# PRUC-Voltmeter_FPGA-Power.net
KiCad netlist of a schematic drawn in Altium Designer
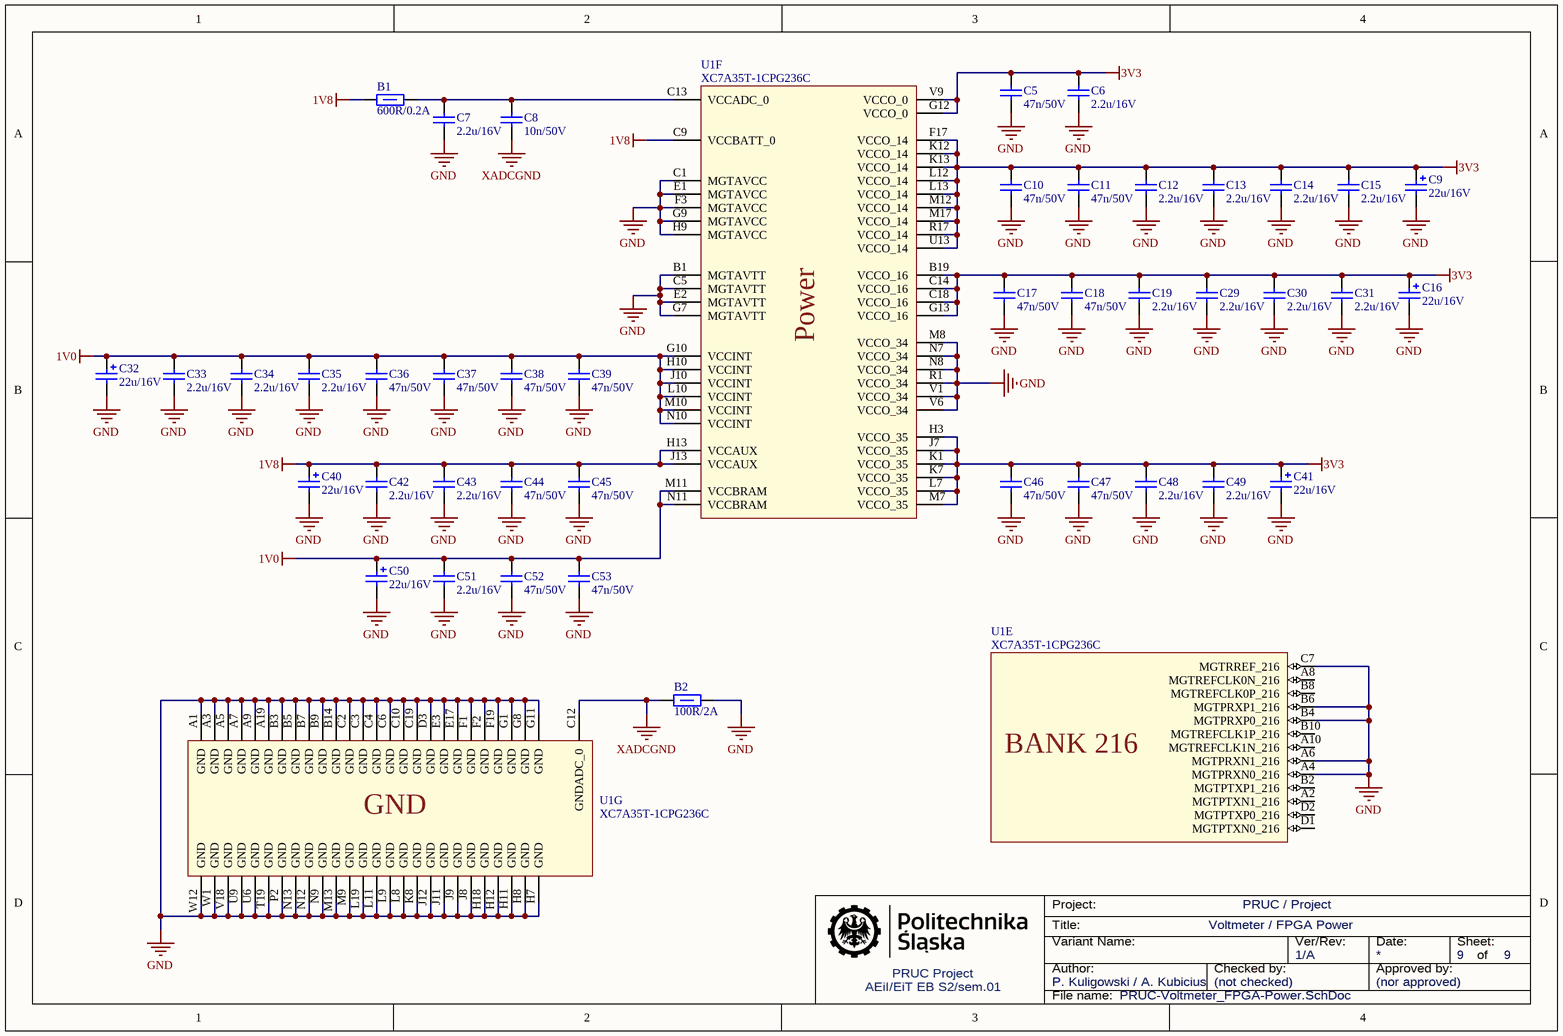
[diagram p0: PRUC-Voltmeter_FPGA-Power.SchDoc]

(export (version "E")
  (design (tool "Eeschema 10.0.6"))
  (components
    (comp (ref "B1")
      (value "600R/0.2A")
      (footprint "FerriteBead_1206")
      (fields
        (field (name "PART NUMBER") "BLM31A601SPT")
        (field (name "MANUFACTURER") "Murata")
        (field (name "MANUFACTURER PART NUMBER") "BLM31AJ601SN1L")
      )
      (libsource (lib "kplabs") (part "FerriteBead"))
    )
    (comp (ref "B2")
      (value "100R/2A")
      (footprint "FerriteBead_0603")
      (fields (field (name "PART NUMBER") "BLM18EG101TN1D") (field (name "MANUFACTURER") "Murata"))
      (libsource (lib "") (part "FerriteBead_1"))
    )
    (comp (ref "C5")
      (value "47n/50V")
      (footprint "MLCC_0603")
      (fields (field (name "PART NUMBER") "CL10B473KB8NNNC") (field (name "MANUFACTURER") "Samsung"))
      (libsource (lib "kplabs") (part "Cap"))
    )
    (comp (ref "C6")
      (value "2.2u/16V")
      (footprint "MLCC_0603")
      (fields (field (name "PART NUMBER") "CL10A225KO8NNNC") (field (name "MANUFACTURER") "Samsung"))
      (libsource (lib "kplabs") (part "Cap"))
    )
    (comp (ref "C7")
      (value "2.2u/16V")
      (footprint "MLCC_0603")
      (fields (field (name "PART NUMBER") "CL10A225KO8NNNC") (field (name "MANUFACTURER") "Samsung"))
      (libsource (lib "kplabs") (part "Cap"))
    )
    (comp (ref "C8")
      (value "10n/50V")
      (footprint "MLCC_0603")
      (fields (field (name "PART NUMBER") "CL10B103KB8NNNC") (field (name "MANUFACTURER") "Samsung"))
      (libsource (lib "kplabs") (part "Cap"))
    )
    (comp (ref "C9")
      (value "22u/16V")
      (footprint "Tantalum_B")
      (fields
        (field (name "PART NUMBER") "TAJB226K016R")
        (field (name "MANUFACTURER") "AVX")
        (field (name "MANUFACTURER PART NUMBER") "TAJB226K016RNJ")
      )
      (libsource (lib "kplabs") (part "Cap_Pol"))
    )
    (comp (ref "C10")
      (value "47n/50V")
      (footprint "MLCC_0603")
      (fields (field (name "PART NUMBER") "CL10B473KB8NNNC") (field (name "MANUFACTURER") "Samsung"))
      (libsource (lib "kplabs") (part "Cap"))
    )
    (comp (ref "C11")
      (value "47n/50V")
      (footprint "MLCC_0603")
      (fields (field (name "PART NUMBER") "CL10B473KB8NNNC") (field (name "MANUFACTURER") "Samsung"))
      (libsource (lib "kplabs") (part "Cap"))
    )
    (comp (ref "C12")
      (value "2.2u/16V")
      (footprint "MLCC_0603")
      (fields (field (name "PART NUMBER") "CL10A225KO8NNNC") (field (name "MANUFACTURER") "Samsung"))
      (libsource (lib "kplabs") (part "Cap"))
    )
    (comp (ref "C13")
      (value "2.2u/16V")
      (footprint "MLCC_0603")
      (fields (field (name "PART NUMBER") "CL10A225KO8NNNC") (field (name "MANUFACTURER") "Samsung"))
      (libsource (lib "kplabs") (part "Cap"))
    )
    (comp (ref "C14")
      (value "2.2u/16V")
      (footprint "MLCC_0603")
      (fields (field (name "PART NUMBER") "CL10A225KO8NNNC") (field (name "MANUFACTURER") "Samsung"))
      (libsource (lib "kplabs") (part "Cap"))
    )
    (comp (ref "C15")
      (value "2.2u/16V")
      (footprint "MLCC_0603")
      (fields (field (name "PART NUMBER") "CL10A225KO8NNNC") (field (name "MANUFACTURER") "Samsung"))
      (libsource (lib "kplabs") (part "Cap"))
    )
    (comp (ref "C16")
      (value "22u/16V")
      (footprint "Tantalum_B")
      (fields
        (field (name "PART NUMBER") "TAJB226K016R")
        (field (name "MANUFACTURER") "AVX")
        (field (name "MANUFACTURER PART NUMBER") "TAJB226K016RNJ")
      )
      (libsource (lib "kplabs") (part "Cap_Pol"))
    )
    (comp (ref "C17")
      (value "47n/50V")
      (footprint "MLCC_0603")
      (fields (field (name "PART NUMBER") "CL10B473KB8NNNC") (field (name "MANUFACTURER") "Samsung"))
      (libsource (lib "kplabs") (part "Cap"))
    )
    (comp (ref "C18")
      (value "47n/50V")
      (footprint "MLCC_0603")
      (fields (field (name "PART NUMBER") "CL10B473KB8NNNC") (field (name "MANUFACTURER") "Samsung"))
      (libsource (lib "kplabs") (part "Cap"))
    )
    (comp (ref "C19")
      (value "2.2u/16V")
      (footprint "MLCC_0603")
      (fields (field (name "PART NUMBER") "CL10A225KO8NNNC") (field (name "MANUFACTURER") "Samsung"))
      (libsource (lib "kplabs") (part "Cap"))
    )
    (comp (ref "C29")
      (value "2.2u/16V")
      (footprint "MLCC_0603")
      (fields (field (name "PART NUMBER") "CL10A225KO8NNNC") (field (name "MANUFACTURER") "Samsung"))
      (libsource (lib "kplabs") (part "Cap"))
    )
    (comp (ref "C30")
      (value "2.2u/16V")
      (footprint "MLCC_0603")
      (fields (field (name "PART NUMBER") "CL10A225KO8NNNC") (field (name "MANUFACTURER") "Samsung"))
      (libsource (lib "kplabs") (part "Cap"))
    )
    (comp (ref "C31")
      (value "2.2u/16V")
      (footprint "MLCC_0603")
      (fields (field (name "PART NUMBER") "CL10A225KO8NNNC") (field (name "MANUFACTURER") "Samsung"))
      (libsource (lib "kplabs") (part "Cap"))
    )
    (comp (ref "C32")
      (value "22u/16V")
      (footprint "Tantalum_B")
      (fields
        (field (name "PART NUMBER") "TAJB226K016R")
        (field (name "MANUFACTURER") "AVX")
        (field (name "MANUFACTURER PART NUMBER") "TAJB226K016RNJ")
      )
      (libsource (lib "kplabs") (part "Cap_Pol"))
    )
    (comp (ref "C33")
      (value "2.2u/16V")
      (footprint "MLCC_0603")
      (fields (field (name "PART NUMBER") "CL10A225KO8NNNC") (field (name "MANUFACTURER") "Samsung"))
      (libsource (lib "kplabs") (part "Cap"))
    )
    (comp (ref "C34")
      (value "2.2u/16V")
      (footprint "MLCC_0603")
      (fields (field (name "PART NUMBER") "CL10A225KO8NNNC") (field (name "MANUFACTURER") "Samsung"))
      (libsource (lib "kplabs") (part "Cap"))
    )
    (comp (ref "C35")
      (value "2.2u/16V")
      (footprint "MLCC_0603")
      (fields (field (name "PART NUMBER") "CL10A225KO8NNNC") (field (name "MANUFACTURER") "Samsung"))
      (libsource (lib "kplabs") (part "Cap"))
    )
    (comp (ref "C36")
      (value "47n/50V")
      (footprint "MLCC_0603")
      (fields (field (name "PART NUMBER") "CL10B473KB8NNNC") (field (name "MANUFACTURER") "Samsung"))
      (libsource (lib "kplabs") (part "Cap"))
    )
    (comp (ref "C37")
      (value "47n/50V")
      (footprint "MLCC_0603")
      (fields (field (name "PART NUMBER") "CL10B473KB8NNNC") (field (name "MANUFACTURER") "Samsung"))
      (libsource (lib "kplabs") (part "Cap"))
    )
    (comp (ref "C38")
      (value "47n/50V")
      (footprint "MLCC_0603")
      (fields (field (name "PART NUMBER") "CL10B473KB8NNNC") (field (name "MANUFACTURER") "Samsung"))
      (libsource (lib "kplabs") (part "Cap"))
    )
    (comp (ref "C39")
      (value "47n/50V")
      (footprint "MLCC_0603")
      (fields (field (name "PART NUMBER") "CL10B473KB8NNNC") (field (name "MANUFACTURER") "Samsung"))
      (libsource (lib "kplabs") (part "Cap"))
    )
    (comp (ref "C40")
      (value "22u/16V")
      (footprint "Tantalum_B")
      (fields
        (field (name "PART NUMBER") "TAJB226K016R")
        (field (name "MANUFACTURER") "AVX")
        (field (name "MANUFACTURER PART NUMBER") "TAJB226K016RNJ")
      )
      (libsource (lib "kplabs") (part "Cap_Pol"))
    )
    (comp (ref "C41")
      (value "22u/16V")
      (footprint "Tantalum_B")
      (fields
        (field (name "PART NUMBER") "TAJB226K016R")
        (field (name "MANUFACTURER") "AVX")
        (field (name "MANUFACTURER PART NUMBER") "TAJB226K016RNJ")
      )
      (libsource (lib "kplabs") (part "Cap_Pol"))
    )
    (comp (ref "C42")
      (value "2.2u/16V")
      (footprint "MLCC_0603")
      (fields (field (name "PART NUMBER") "CL10A225KO8NNNC") (field (name "MANUFACTURER") "Samsung"))
      (libsource (lib "kplabs") (part "Cap"))
    )
    (comp (ref "C43")
      (value "2.2u/16V")
      (footprint "MLCC_0603")
      (fields (field (name "PART NUMBER") "CL10A225KO8NNNC") (field (name "MANUFACTURER") "Samsung"))
      (libsource (lib "kplabs") (part "Cap"))
    )
    (comp (ref "C44")
      (value "47n/50V")
      (footprint "MLCC_0603")
      (fields (field (name "PART NUMBER") "CL10B473KB8NNNC") (field (name "MANUFACTURER") "Samsung"))
      (libsource (lib "kplabs") (part "Cap"))
    )
    (comp (ref "C45")
      (value "47n/50V")
      (footprint "MLCC_0603")
      (fields (field (name "PART NUMBER") "CL10B473KB8NNNC") (field (name "MANUFACTURER") "Samsung"))
      (libsource (lib "kplabs") (part "Cap"))
    )
    (comp (ref "C46")
      (value "47n/50V")
      (footprint "MLCC_0603")
      (fields (field (name "PART NUMBER") "CL10B473KB8NNNC") (field (name "MANUFACTURER") "Samsung"))
      (libsource (lib "kplabs") (part "Cap"))
    )
    (comp (ref "C47")
      (value "47n/50V")
      (footprint "MLCC_0603")
      (fields (field (name "PART NUMBER") "CL10B473KB8NNNC") (field (name "MANUFACTURER") "Samsung"))
      (libsource (lib "kplabs") (part "Cap"))
    )
    (comp (ref "C48")
      (value "2.2u/16V")
      (footprint "MLCC_0603")
      (fields (field (name "PART NUMBER") "CL10A225KO8NNNC") (field (name "MANUFACTURER") "Samsung"))
      (libsource (lib "kplabs") (part "Cap"))
    )
    (comp (ref "C49")
      (value "2.2u/16V")
      (footprint "MLCC_0603")
      (fields (field (name "PART NUMBER") "CL10A225KO8NNNC") (field (name "MANUFACTURER") "Samsung"))
      (libsource (lib "kplabs") (part "Cap"))
    )
    (comp (ref "C50")
      (value "22u/16V")
      (footprint "Tantalum_B")
      (fields
        (field (name "PART NUMBER") "TAJB226K016R")
        (field (name "MANUFACTURER") "AVX")
        (field (name "MANUFACTURER PART NUMBER") "TAJB226K016RNJ")
      )
      (libsource (lib "kplabs") (part "Cap_Pol"))
    )
    (comp (ref "C51")
      (value "2.2u/16V")
      (footprint "MLCC_0603")
      (fields (field (name "PART NUMBER") "CL10A225KO8NNNC") (field (name "MANUFACTURER") "Samsung"))
      (libsource (lib "kplabs") (part "Cap"))
    )
    (comp (ref "C52")
      (value "47n/50V")
      (footprint "MLCC_0603")
      (fields (field (name "PART NUMBER") "CL10B473KB8NNNC") (field (name "MANUFACTURER") "Samsung"))
      (libsource (lib "kplabs") (part "Cap"))
    )
    (comp (ref "C53")
      (value "47n/50V")
      (footprint "MLCC_0603")
      (fields (field (name "PART NUMBER") "CL10B473KB8NNNC") (field (name "MANUFACTURER") "Samsung"))
      (libsource (lib "kplabs") (part "Cap"))
    )
    (comp (ref "U1")
      (value "XC7A35T-1CPG236C")
      (footprint "CPG236-0.5mm")
      (fields (field (name "MANUFACTURER") "Xilinx"))
      (libsource (lib "kplabs") (part "XC7A35T-1CPG236C"))
    )
  )
  (nets
    (net (code "1") (name "1V0") (class "Default")
      (node (ref "C32") (pin "1") (pinfunction "1_1") (pintype "passive"))
      (node (ref "C33") (pin "1") (pinfunction "1_1") (pintype "passive"))
      (node (ref "C34") (pin "1") (pinfunction "1_1") (pintype "passive"))
      (node (ref "C35") (pin "1") (pinfunction "1_1") (pintype "passive"))
      (node (ref "C36") (pin "1") (pinfunction "1_1") (pintype "passive"))
      (node (ref "C37") (pin "1") (pinfunction "1_1") (pintype "passive"))
      (node (ref "C38") (pin "1") (pinfunction "1_1") (pintype "passive"))
      (node (ref "C39") (pin "1") (pinfunction "1_1") (pintype "passive"))
      (node (ref "C50") (pin "1") (pinfunction "1_1") (pintype "passive"))
      (node (ref "C51") (pin "1") (pinfunction "1_1") (pintype "passive"))
      (node (ref "C52") (pin "1") (pinfunction "1_1") (pintype "passive"))
      (node (ref "C53") (pin "1") (pinfunction "1_1") (pintype "passive"))
      (node (ref "U1") (pin "G10") (pinfunction "VCCINT_G10") (pintype "power_in"))
      (node (ref "U1") (pin "H10") (pinfunction "VCCINT_H10") (pintype "power_in"))
      (node (ref "U1") (pin "J10") (pinfunction "VCCINT_J10") (pintype "power_in"))
      (node (ref "U1") (pin "L10") (pinfunction "VCCINT_L10") (pintype "power_in"))
      (node (ref "U1") (pin "M10") (pinfunction "VCCINT_M10") (pintype "power_in"))
      (node (ref "U1") (pin "M11") (pinfunction "VCCBRAM_M11") (pintype "power_in"))
      (node (ref "U1") (pin "N10") (pinfunction "VCCINT_N10") (pintype "power_in"))
      (node (ref "U1") (pin "N11") (pinfunction "VCCBRAM_N11") (pintype "power_in"))
    )
    (net (code "2") (name "1V8") (class "Default")
      (node (ref "B1") (pin "2") (pinfunction "2_2") (pintype "passive"))
      (node (ref "C40") (pin "1") (pinfunction "1_1") (pintype "passive"))
      (node (ref "C42") (pin "1") (pinfunction "1_1") (pintype "passive"))
      (node (ref "C43") (pin "1") (pinfunction "1_1") (pintype "passive"))
      (node (ref "C44") (pin "1") (pinfunction "1_1") (pintype "passive"))
      (node (ref "C45") (pin "1") (pinfunction "1_1") (pintype "passive"))
      (node (ref "U1") (pin "C9") (pinfunction "VCCBATT_0_C9") (pintype "power_in"))
      (node (ref "U1") (pin "H13") (pinfunction "VCCAUX_H13") (pintype "power_in"))
      (node (ref "U1") (pin "J13") (pinfunction "VCCAUX_J13") (pintype "power_in"))
    )
    (net (code "3") (name "3V3") (class "Default")
      (node (ref "C10") (pin "1") (pinfunction "1_1") (pintype "passive"))
      (node (ref "C11") (pin "1") (pinfunction "1_1") (pintype "passive"))
      (node (ref "C12") (pin "1") (pinfunction "1_1") (pintype "passive"))
      (node (ref "C13") (pin "1") (pinfunction "1_1") (pintype "passive"))
      (node (ref "C14") (pin "1") (pinfunction "1_1") (pintype "passive"))
      (node (ref "C15") (pin "1") (pinfunction "1_1") (pintype "passive"))
      (node (ref "C16") (pin "1") (pinfunction "1_1") (pintype "passive"))
      (node (ref "C17") (pin "1") (pinfunction "1_1") (pintype "passive"))
      (node (ref "C18") (pin "1") (pinfunction "1_1") (pintype "passive"))
      (node (ref "C19") (pin "1") (pinfunction "1_1") (pintype "passive"))
      (node (ref "C29") (pin "1") (pinfunction "1_1") (pintype "passive"))
      (node (ref "C30") (pin "1") (pinfunction "1_1") (pintype "passive"))
      (node (ref "C31") (pin "1") (pinfunction "1_1") (pintype "passive"))
      (node (ref "C41") (pin "1") (pinfunction "1_1") (pintype "passive"))
      (node (ref "C46") (pin "1") (pinfunction "1_1") (pintype "passive"))
      (node (ref "C47") (pin "1") (pinfunction "1_1") (pintype "passive"))
      (node (ref "C48") (pin "1") (pinfunction "1_1") (pintype "passive"))
      (node (ref "C49") (pin "1") (pinfunction "1_1") (pintype "passive"))
      (node (ref "C5") (pin "1") (pinfunction "1_1") (pintype "passive"))
      (node (ref "C6") (pin "1") (pinfunction "1_1") (pintype "passive"))
      (node (ref "C9") (pin "1") (pinfunction "1_1") (pintype "passive"))
      (node (ref "U1") (pin "B19") (pinfunction "VCCO_16_B19") (pintype "power_in"))
      (node (ref "U1") (pin "C14") (pinfunction "VCCO_16_C14") (pintype "power_in"))
      (node (ref "U1") (pin "C18") (pinfunction "VCCO_16_C18") (pintype "power_in"))
      (node (ref "U1") (pin "F17") (pinfunction "VCCO_14_F17") (pintype "power_in"))
      (node (ref "U1") (pin "G12") (pinfunction "VCCO_0_G12") (pintype "power_in"))
      (node (ref "U1") (pin "G13") (pinfunction "VCCO_16_G13") (pintype "power_in"))
      (node (ref "U1") (pin "H3") (pinfunction "VCCO_35_H3") (pintype "power_in"))
      (node (ref "U1") (pin "J7") (pinfunction "VCCO_35_J7") (pintype "power_in"))
      (node (ref "U1") (pin "K1") (pinfunction "VCCO_35_K1") (pintype "power_in"))
      (node (ref "U1") (pin "K12") (pinfunction "VCCO_14_K12") (pintype "power_in"))
      (node (ref "U1") (pin "K13") (pinfunction "VCCO_14_K13") (pintype "power_in"))
      (node (ref "U1") (pin "K7") (pinfunction "VCCO_35_K7") (pintype "power_in"))
      (node (ref "U1") (pin "L12") (pinfunction "VCCO_14_L12") (pintype "power_in"))
      (node (ref "U1") (pin "L13") (pinfunction "VCCO_14_L13") (pintype "power_in"))
      (node (ref "U1") (pin "L7") (pinfunction "VCCO_35_L7") (pintype "power_in"))
      (node (ref "U1") (pin "M12") (pinfunction "VCCO_14_M12") (pintype "power_in"))
      (node (ref "U1") (pin "M17") (pinfunction "VCCO_14_M17") (pintype "power_in"))
      (node (ref "U1") (pin "M7") (pinfunction "VCCO_35_M7") (pintype "power_in"))
      (node (ref "U1") (pin "R17") (pinfunction "VCCO_14_R17") (pintype "power_in"))
      (node (ref "U1") (pin "U13") (pinfunction "VCCO_14_U13") (pintype "power_in"))
      (node (ref "U1") (pin "V9") (pinfunction "VCCO_0_V9") (pintype "power_in"))
    )
    (net (code "4") (name "GND") (class "Default")
      (node (ref "B2") (pin "2") (pinfunction "2_2") (pintype "passive"))
      (node (ref "C10") (pin "2") (pinfunction "2_2") (pintype "passive"))
      (node (ref "C11") (pin "2") (pinfunction "2_2") (pintype "passive"))
      (node (ref "C12") (pin "2") (pinfunction "2_2") (pintype "passive"))
      (node (ref "C13") (pin "2") (pinfunction "2_2") (pintype "passive"))
      (node (ref "C14") (pin "2") (pinfunction "2_2") (pintype "passive"))
      (node (ref "C15") (pin "2") (pinfunction "2_2") (pintype "passive"))
      (node (ref "C16") (pin "2") (pinfunction "2_2") (pintype "passive"))
      (node (ref "C17") (pin "2") (pinfunction "2_2") (pintype "passive"))
      (node (ref "C18") (pin "2") (pinfunction "2_2") (pintype "passive"))
      (node (ref "C19") (pin "2") (pinfunction "2_2") (pintype "passive"))
      (node (ref "C29") (pin "2") (pinfunction "2_2") (pintype "passive"))
      (node (ref "C30") (pin "2") (pinfunction "2_2") (pintype "passive"))
      (node (ref "C31") (pin "2") (pinfunction "2_2") (pintype "passive"))
      (node (ref "C32") (pin "2") (pinfunction "2_2") (pintype "passive"))
      (node (ref "C33") (pin "2") (pinfunction "2_2") (pintype "passive"))
      (node (ref "C34") (pin "2") (pinfunction "2_2") (pintype "passive"))
      (node (ref "C35") (pin "2") (pinfunction "2_2") (pintype "passive"))
      (node (ref "C36") (pin "2") (pinfunction "2_2") (pintype "passive"))
      (node (ref "C37") (pin "2") (pinfunction "2_2") (pintype "passive"))
      (node (ref "C38") (pin "2") (pinfunction "2_2") (pintype "passive"))
      (node (ref "C39") (pin "2") (pinfunction "2_2") (pintype "passive"))
      (node (ref "C40") (pin "2") (pinfunction "2_2") (pintype "passive"))
      (node (ref "C41") (pin "2") (pinfunction "2_2") (pintype "passive"))
      (node (ref "C42") (pin "2") (pinfunction "2_2") (pintype "passive"))
      (node (ref "C43") (pin "2") (pinfunction "2_2") (pintype "passive"))
      (node (ref "C44") (pin "2") (pinfunction "2_2") (pintype "passive"))
      (node (ref "C45") (pin "2") (pinfunction "2_2") (pintype "passive"))
      (node (ref "C46") (pin "2") (pinfunction "2_2") (pintype "passive"))
      (node (ref "C47") (pin "2") (pinfunction "2_2") (pintype "passive"))
      (node (ref "C48") (pin "2") (pinfunction "2_2") (pintype "passive"))
      (node (ref "C49") (pin "2") (pinfunction "2_2") (pintype "passive"))
      (node (ref "C5") (pin "2") (pinfunction "2_2") (pintype "passive"))
      (node (ref "C50") (pin "2") (pinfunction "2_2") (pintype "passive"))
      (node (ref "C51") (pin "2") (pinfunction "2_2") (pintype "passive"))
      (node (ref "C52") (pin "2") (pinfunction "2_2") (pintype "passive"))
      (node (ref "C53") (pin "2") (pinfunction "2_2") (pintype "passive"))
      (node (ref "C6") (pin "2") (pinfunction "2_2") (pintype "passive"))
      (node (ref "C7") (pin "2") (pinfunction "2_2") (pintype "passive"))
      (node (ref "C9") (pin "2") (pinfunction "2_2") (pintype "passive"))
      (node (ref "U1") (pin "A1") (pinfunction "GND_A1") (pintype "power_in"))
      (node (ref "U1") (pin "A19") (pinfunction "GND_A19") (pintype "power_in"))
      (node (ref "U1") (pin "A3") (pinfunction "GND_A3") (pintype "power_in"))
      (node (ref "U1") (pin "A4") (pinfunction "MGTPRXN0_216_A4") (pintype "bidirectional"))
      (node (ref "U1") (pin "A5") (pinfunction "GND_A5") (pintype "power_in"))
      (node (ref "U1") (pin "A6") (pinfunction "MGTPRXN1_216_A6") (pintype "bidirectional"))
      (node (ref "U1") (pin "A7") (pinfunction "GND_A7") (pintype "power_in"))
      (node (ref "U1") (pin "A9") (pinfunction "GND_A9") (pintype "power_in"))
      (node (ref "U1") (pin "B1") (pinfunction "MGTAVTT_B1") (pintype "power_in"))
      (node (ref "U1") (pin "B14") (pinfunction "GND_B14") (pintype "power_in"))
      (node (ref "U1") (pin "B3") (pinfunction "GND_B3") (pintype "power_in"))
      (node (ref "U1") (pin "B4") (pinfunction "MGTPRXP0_216_B4") (pintype "bidirectional"))
      (node (ref "U1") (pin "B5") (pinfunction "GND_B5") (pintype "power_in"))
      (node (ref "U1") (pin "B6") (pinfunction "MGTPRXP1_216_B6") (pintype "bidirectional"))
      (node (ref "U1") (pin "B7") (pinfunction "GND_B7") (pintype "power_in"))
      (node (ref "U1") (pin "B9") (pinfunction "GND_B9") (pintype "power_in"))
      (node (ref "U1") (pin "C1") (pinfunction "MGTAVCC_C1") (pintype "power_in"))
      (node (ref "U1") (pin "C10") (pinfunction "GND_C10") (pintype "power_in"))
      (node (ref "U1") (pin "C19") (pinfunction "GND_C19") (pintype "power_in"))
      (node (ref "U1") (pin "C2") (pinfunction "GND_C2") (pintype "power_in"))
      (node (ref "U1") (pin "C3") (pinfunction "GND_C3") (pintype "power_in"))
      (node (ref "U1") (pin "C4") (pinfunction "GND_C4") (pintype "power_in"))
      (node (ref "U1") (pin "C5") (pinfunction "MGTAVTT_C5") (pintype "power_in"))
      (node (ref "U1") (pin "C6") (pinfunction "GND_C6") (pintype "power_in"))
      (node (ref "U1") (pin "C7") (pinfunction "MGTRREF_216_C7") (pintype "bidirectional"))
      (node (ref "U1") (pin "D3") (pinfunction "GND_D3") (pintype "power_in"))
      (node (ref "U1") (pin "E1") (pinfunction "MGTAVCC_E1") (pintype "power_in"))
      (node (ref "U1") (pin "E17") (pinfunction "GND_E17") (pintype "power_in"))
      (node (ref "U1") (pin "E2") (pinfunction "MGTAVTT_E2") (pintype "power_in"))
      (node (ref "U1") (pin "E3") (pinfunction "GND_E3") (pintype "power_in"))
      (node (ref "U1") (pin "F1") (pinfunction "GND_F1") (pintype "power_in"))
      (node (ref "U1") (pin "F19") (pinfunction "GND_F19") (pintype "power_in"))
      (node (ref "U1") (pin "F2") (pinfunction "GND_F2") (pintype "power_in"))
      (node (ref "U1") (pin "F3") (pinfunction "MGTAVCC_F3") (pintype "power_in"))
      (node (ref "U1") (pin "G1") (pinfunction "GND_G1") (pintype "power_in"))
      (node (ref "U1") (pin "G11") (pinfunction "GND_G11") (pintype "power_in"))
      (node (ref "U1") (pin "G7") (pinfunction "MGTAVTT_G7") (pintype "power_in"))
      (node (ref "U1") (pin "G8") (pinfunction "GND_G8") (pintype "power_in"))
      (node (ref "U1") (pin "G9") (pinfunction "MGTAVCC_G9") (pintype "power_in"))
      (node (ref "U1") (pin "H11") (pinfunction "GND_H11") (pintype "power_in"))
      (node (ref "U1") (pin "H12") (pinfunction "GND_H12") (pintype "power_in"))
      (node (ref "U1") (pin "H18") (pinfunction "GND_H18") (pintype "power_in"))
      (node (ref "U1") (pin "H7") (pinfunction "GND_H7") (pintype "power_in"))
      (node (ref "U1") (pin "H8") (pinfunction "GND_H8") (pintype "power_in"))
      (node (ref "U1") (pin "H9") (pinfunction "MGTAVCC_H9") (pintype "power_in"))
      (node (ref "U1") (pin "J11") (pinfunction "GND_J11") (pintype "power_in"))
      (node (ref "U1") (pin "J12") (pinfunction "GND_J12") (pintype "power_in"))
      (node (ref "U1") (pin "J8") (pinfunction "GND_J8") (pintype "power_in"))
      (node (ref "U1") (pin "J9") (pinfunction "GND_J9") (pintype "power_in"))
      (node (ref "U1") (pin "K8") (pinfunction "GND_K8") (pintype "power_in"))
      (node (ref "U1") (pin "L11") (pinfunction "GND_L11") (pintype "power_in"))
      (node (ref "U1") (pin "L19") (pinfunction "GND_L19") (pintype "power_in"))
      (node (ref "U1") (pin "L8") (pinfunction "GND_L8") (pintype "power_in"))
      (node (ref "U1") (pin "L9") (pinfunction "GND_L9") (pintype "power_in"))
      (node (ref "U1") (pin "M13") (pinfunction "GND_M13") (pintype "power_in"))
      (node (ref "U1") (pin "M8") (pinfunction "VCCO_34_M8") (pintype "power_in"))
      (node (ref "U1") (pin "M9") (pinfunction "GND_M9") (pintype "power_in"))
      (node (ref "U1") (pin "N12") (pinfunction "GND_N12") (pintype "power_in"))
      (node (ref "U1") (pin "N13") (pinfunction "GND_N13") (pintype "power_in"))
      (node (ref "U1") (pin "N7") (pinfunction "VCCO_34_N7") (pintype "power_in"))
      (node (ref "U1") (pin "N8") (pinfunction "VCCO_34_N8") (pintype "power_in"))
      (node (ref "U1") (pin "N9") (pinfunction "GND_N9") (pintype "power_in"))
      (node (ref "U1") (pin "P2") (pinfunction "GND_P2") (pintype "power_in"))
      (node (ref "U1") (pin "R1") (pinfunction "VCCO_34_R1") (pintype "power_in"))
      (node (ref "U1") (pin "T19") (pinfunction "GND_T19") (pintype "power_in"))
      (node (ref "U1") (pin "U6") (pinfunction "GND_U6") (pintype "power_in"))
      (node (ref "U1") (pin "U9") (pinfunction "GND_U9") (pintype "power_in"))
      (node (ref "U1") (pin "V1") (pinfunction "VCCO_34_V1") (pintype "power_in"))
      (node (ref "U1") (pin "V18") (pinfunction "GND_V18") (pintype "power_in"))
      (node (ref "U1") (pin "V6") (pinfunction "VCCO_34_V6") (pintype "power_in"))
      (node (ref "U1") (pin "W1") (pinfunction "GND_W1") (pintype "power_in"))
      (node (ref "U1") (pin "W12") (pinfunction "GND_W12") (pintype "power_in"))
    )
    (net (code "5") (name "Net-(U1F-VCCADC_0)") (class "Default")
      (node (ref "B1") (pin "1") (pinfunction "1_1") (pintype "passive"))
      (node (ref "C7") (pin "1") (pinfunction "1_1") (pintype "passive"))
      (node (ref "C8") (pin "1") (pinfunction "1_1") (pintype "passive"))
      (node (ref "U1") (pin "C13") (pinfunction "VCCADC_0_C13") (pintype "power_in"))
    )
    (net (code "6") (name "XADCGND") (class "Default")
      (node (ref "B2") (pin "1") (pinfunction "1_1") (pintype "passive"))
      (node (ref "C8") (pin "2") (pinfunction "2_2") (pintype "passive"))
      (node (ref "U1") (pin "C12") (pinfunction "GNDADC_0_C12") (pintype "power_in"))
    )
    (net (code "7") (name "unconnected-(U1E-MGTPTXN0_216-PadD1)") (class "Default")
      (node (ref "U1") (pin "D1") (pinfunction "MGTPTXN0_216_D1") (pintype "bidirectional"))
    )
    (net (code "8") (name "unconnected-(U1E-MGTPTXN1_216-PadA2)") (class "Default")
      (node (ref "U1") (pin "A2") (pinfunction "MGTPTXN1_216_A2") (pintype "bidirectional"))
    )
    (net (code "9") (name "unconnected-(U1E-MGTPTXP0_216-PadD2)") (class "Default")
      (node (ref "U1") (pin "D2") (pinfunction "MGTPTXP0_216_D2") (pintype "bidirectional"))
    )
    (net (code "10") (name "unconnected-(U1E-MGTPTXP1_216-PadB2)") (class "Default")
      (node (ref "U1") (pin "B2") (pinfunction "MGTPTXP1_216_B2") (pintype "bidirectional"))
    )
    (net (code "11") (name "unconnected-(U1E-MGTREFCLK0N_216-PadA8)") (class "Default")
      (node (ref "U1") (pin "A8") (pinfunction "MGTREFCLK0N_216_A8") (pintype "bidirectional"))
    )
    (net (code "12") (name "unconnected-(U1E-MGTREFCLK0P_216-PadB8)") (class "Default")
      (node (ref "U1") (pin "B8") (pinfunction "MGTREFCLK0P_216_B8") (pintype "bidirectional"))
    )
    (net (code "13") (name "unconnected-(U1E-MGTREFCLK1N_216-PadA10)") (class "Default")
      (node (ref "U1") (pin "A10") (pinfunction "MGTREFCLK1N_216_A10") (pintype "bidirectional"))
    )
    (net (code "14") (name "unconnected-(U1E-MGTREFCLK1P_216-PadB10)") (class "Default")
      (node (ref "U1") (pin "B10") (pinfunction "MGTREFCLK1P_216_B10") (pintype "bidirectional"))
    )
  )
)
